# Auxilary.net
KiCad netlist of a schematic drawn in Altium Designer
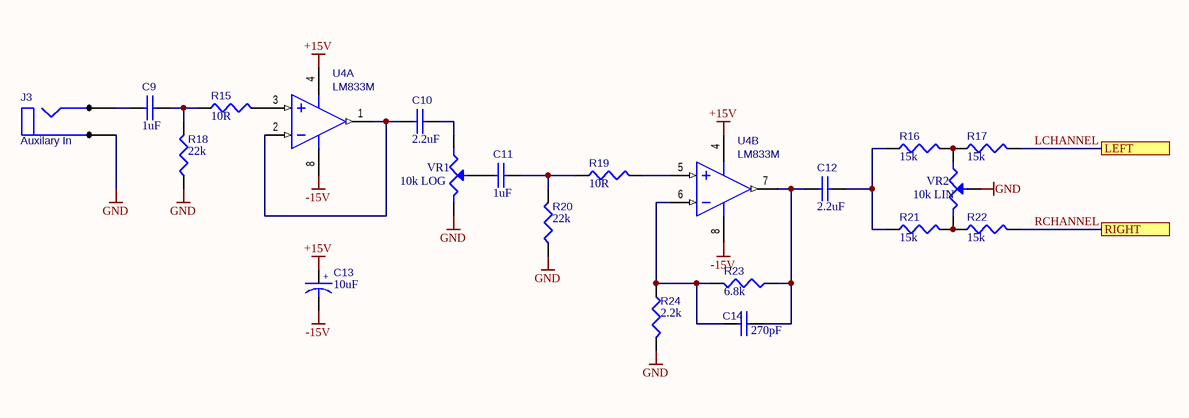
[diagram p0: Auxilary.SchDoc]

(export (version "E")
  (design (tool "Eeschema 10.0.6"))
  (components
    (comp (ref "C9")
      (value "1uF")
      (footprint "RB.2/.4-NP")
      (description "Capacitor")
      (libsource (lib "*") (part "CAP"))
    )
    (comp (ref "C10")
      (value "2.2uF")
      (footprint "RB.2/.4-NP")
      (description "Capacitor")
      (libsource (lib "*") (part "CAP"))
    )
    (comp (ref "C11")
      (value "1uF")
      (footprint "RB.2/.4-NP")
      (description "Capacitor")
      (libsource (lib "*") (part "CAP"))
    )
    (comp (ref "C12")
      (value "2.2uF")
      (footprint "RB.2/.4-NP")
      (description "Capacitor")
      (libsource (lib "*") (part "CAP"))
    )
    (comp (ref "C13")
      (value "10uF")
      (footprint "RB.2/.4")
      (description "Bi-Polar Capacitor")
      (libsource (lib "*") (part "CAPACITOR POL"))
    )
    (comp (ref "C14")
      (value "270pF")
      (footprint "RAD0.2")
      (description "Capacitor")
      (libsource (lib "*") (part "CAP"))
    )
    (comp (ref "J3")
      (value "Auxilary In")
      (footprint "JACK-6.25MM")
      (libsource (lib "*") (part "PHONEJACK MONO"))
    )
    (comp (ref "R15")
      (value "10R")
      (footprint "AXIAL0.4")
      (description "Resistor")
      (libsource (lib "*") (part "RES1"))
    )
    (comp (ref "R16")
      (value "15k")
      (footprint "AXIAL0.4")
      (description "Resistor")
      (libsource (lib "*") (part "RES1"))
    )
    (comp (ref "R17")
      (value "15k")
      (footprint "AXIAL0.4")
      (description "Resistor")
      (libsource (lib "*") (part "RES1"))
    )
    (comp (ref "R18")
      (value "22k")
      (footprint "AXIAL0.4")
      (description "Resistor")
      (libsource (lib "") (part "RES1_2"))
    )
    (comp (ref "R19")
      (value "10R")
      (footprint "AXIAL0.4")
      (description "Resistor")
      (libsource (lib "*") (part "RES1"))
    )
    (comp (ref "R20")
      (value "22k")
      (footprint "AXIAL0.4")
      (description "Resistor")
      (libsource (lib "") (part "RES1_2"))
    )
    (comp (ref "R21")
      (value "15k")
      (footprint "AXIAL0.4")
      (description "Resistor")
      (libsource (lib "*") (part "RES1"))
    )
    (comp (ref "R22")
      (value "15k")
      (footprint "AXIAL0.4")
      (description "Resistor")
      (libsource (lib "*") (part "RES1"))
    )
    (comp (ref "R23")
      (value "6.8k")
      (footprint "AXIAL0.4")
      (description "Resistor")
      (libsource (lib "") (part "RES1_3"))
    )
    (comp (ref "R24")
      (value "2.2k")
      (footprint "AXIAL0.4")
      (description "Resistor")
      (libsource (lib "") (part "RES1_1"))
    )
    (comp (ref "U4")
      (value "LM833M")
      (footprint "DIP8")
      (description "Fast Settling Dual Operational Amplifier")
      (libsource (lib "*") (part "LM833M"))
    )
    (comp (ref "VR1")
      (value "10k LOG")
      (footprint "POT - 24MM")
      (description "Potentiometer")
      (libsource (lib "*") (part "POT1"))
    )
    (comp (ref "VR2")
      (value "10k LIN")
      (footprint "POT - 24MM")
      (description "Potentiometer")
      (libsource (lib "*") (part "POT1"))
    )
  )
  (nets
    (net (code "1") (name "+15V") (class "Default")
      (node (ref "C13") (pin "1") (pinfunction "1_1") (pintype "passive"))
      (node (ref "U4") (pin "4") (pinfunction "V-_4") (pintype "power_in"))
    )
    (net (code "2") (name "-15V") (class "Default")
      (node (ref "C13") (pin "2") (pinfunction "2_2") (pintype "passive"))
      (node (ref "U4") (pin "8") (pinfunction "V+_8") (pintype "power_in"))
    )
    (net (code "3") (name "/LCHANNEL") (class "Default")
      (node (ref "R17") (pin "2") (pinfunction "2_2") (pintype "passive"))
    )
    (net (code "4") (name "/RCHANNEL") (class "Default")
      (node (ref "R22") (pin "2") (pinfunction "2_2") (pintype "passive"))
    )
    (net (code "5") (name "GND") (class "Default")
      (node (ref "J3") (pin "3") (pinfunction "C_3") (pintype "passive"))
      (node (ref "R18") (pin "1") (pinfunction "1_1") (pintype "passive"))
      (node (ref "R20") (pin "1") (pinfunction "1_1") (pintype "passive"))
      (node (ref "R24") (pin "2") (pinfunction "2_2") (pintype "passive"))
      (node (ref "VR1") (pin "3") (pinfunction "3_3") (pintype "passive"))
      (node (ref "VR2") (pin "2") (pinfunction "W_2") (pintype "passive"))
    )
    (net (code "6") (name "Net-(C9-Pad2)") (class "Default")
      (node (ref "C9") (pin "2") (pinfunction "2_2") (pintype "passive"))
      (node (ref "R15") (pin "1") (pinfunction "1_1") (pintype "passive"))
      (node (ref "R18") (pin "2") (pinfunction "2_2") (pintype "passive"))
    )
    (net (code "7") (name "Net-(C10-Pad2)") (class "Default")
      (node (ref "C10") (pin "2") (pinfunction "2_2") (pintype "passive"))
      (node (ref "VR1") (pin "1") (pinfunction "1_1") (pintype "passive"))
    )
    (net (code "8") (name "Net-(C11-Pad2)") (class "Default")
      (node (ref "C11") (pin "2") (pinfunction "2_2") (pintype "passive"))
      (node (ref "R19") (pin "1") (pinfunction "1_1") (pintype "passive"))
      (node (ref "R20") (pin "2") (pinfunction "2_2") (pintype "passive"))
    )
    (net (code "9") (name "Net-(C12-Pad2)") (class "Default")
      (node (ref "C12") (pin "2") (pinfunction "2_2") (pintype "passive"))
      (node (ref "R16") (pin "1") (pinfunction "1_1") (pintype "passive"))
      (node (ref "R21") (pin "1") (pinfunction "1_1") (pintype "passive"))
    )
    (net (code "10") (name "Net-(J3-A)") (class "Default")
      (node (ref "C9") (pin "1") (pinfunction "1_1") (pintype "passive"))
      (node (ref "J3") (pin "1") (pinfunction "A_1") (pintype "passive"))
    )
    (net (code "11") (name "Net-(R16-Pad2)") (class "Default")
      (node (ref "R16") (pin "2") (pinfunction "2_2") (pintype "passive"))
      (node (ref "R17") (pin "1") (pinfunction "1_1") (pintype "passive"))
      (node (ref "VR2") (pin "1") (pinfunction "1_1") (pintype "passive"))
    )
    (net (code "12") (name "Net-(R21-Pad2)") (class "Default")
      (node (ref "R21") (pin "2") (pinfunction "2_2") (pintype "passive"))
      (node (ref "R22") (pin "1") (pinfunction "1_1") (pintype "passive"))
      (node (ref "VR2") (pin "3") (pinfunction "3_3") (pintype "passive"))
    )
    (net (code "13") (name "Net-(U4A-IN1+)") (class "Default")
      (node (ref "R15") (pin "2") (pinfunction "2_2") (pintype "passive"))
      (node (ref "U4") (pin "3") (pinfunction "IN1+_3") (pintype "input"))
    )
    (net (code "14") (name "Net-(U4A-IN1-)") (class "Default")
      (node (ref "C10") (pin "1") (pinfunction "1_1") (pintype "passive"))
      (node (ref "U4") (pin "1") (pinfunction "OUT1_1") (pintype "output"))
      (node (ref "U4") (pin "2") (pinfunction "IN1-_2") (pintype "input"))
    )
    (net (code "15") (name "Net-(U4B-IN2+)") (class "Default")
      (node (ref "R19") (pin "2") (pinfunction "2_2") (pintype "passive"))
      (node (ref "U4") (pin "5") (pinfunction "IN2+_5") (pintype "input"))
    )
    (net (code "16") (name "Net-(U4B-IN2-)") (class "Default")
      (node (ref "C14") (pin "1") (pinfunction "1_1") (pintype "passive"))
      (node (ref "R23") (pin "2") (pinfunction "2_2") (pintype "passive"))
      (node (ref "R24") (pin "1") (pinfunction "1_1") (pintype "passive"))
      (node (ref "U4") (pin "6") (pinfunction "IN2-_6") (pintype "input"))
    )
    (net (code "17") (name "Net-(U4B-OUT2)") (class "Default")
      (node (ref "C12") (pin "1") (pinfunction "1_1") (pintype "passive"))
      (node (ref "C14") (pin "2") (pinfunction "2_2") (pintype "passive"))
      (node (ref "R23") (pin "1") (pinfunction "1_1") (pintype "passive"))
      (node (ref "U4") (pin "7") (pinfunction "OUT2_7") (pintype "output"))
    )
    (net (code "18") (name "Net-(VR1-W)") (class "Default")
      (node (ref "C11") (pin "1") (pinfunction "1_1") (pintype "passive"))
      (node (ref "VR1") (pin "2") (pinfunction "W_2") (pintype "passive"))
    )
  )
)
